# Schematic.net
KiCad netlist of a schematic drawn in Altium Designer
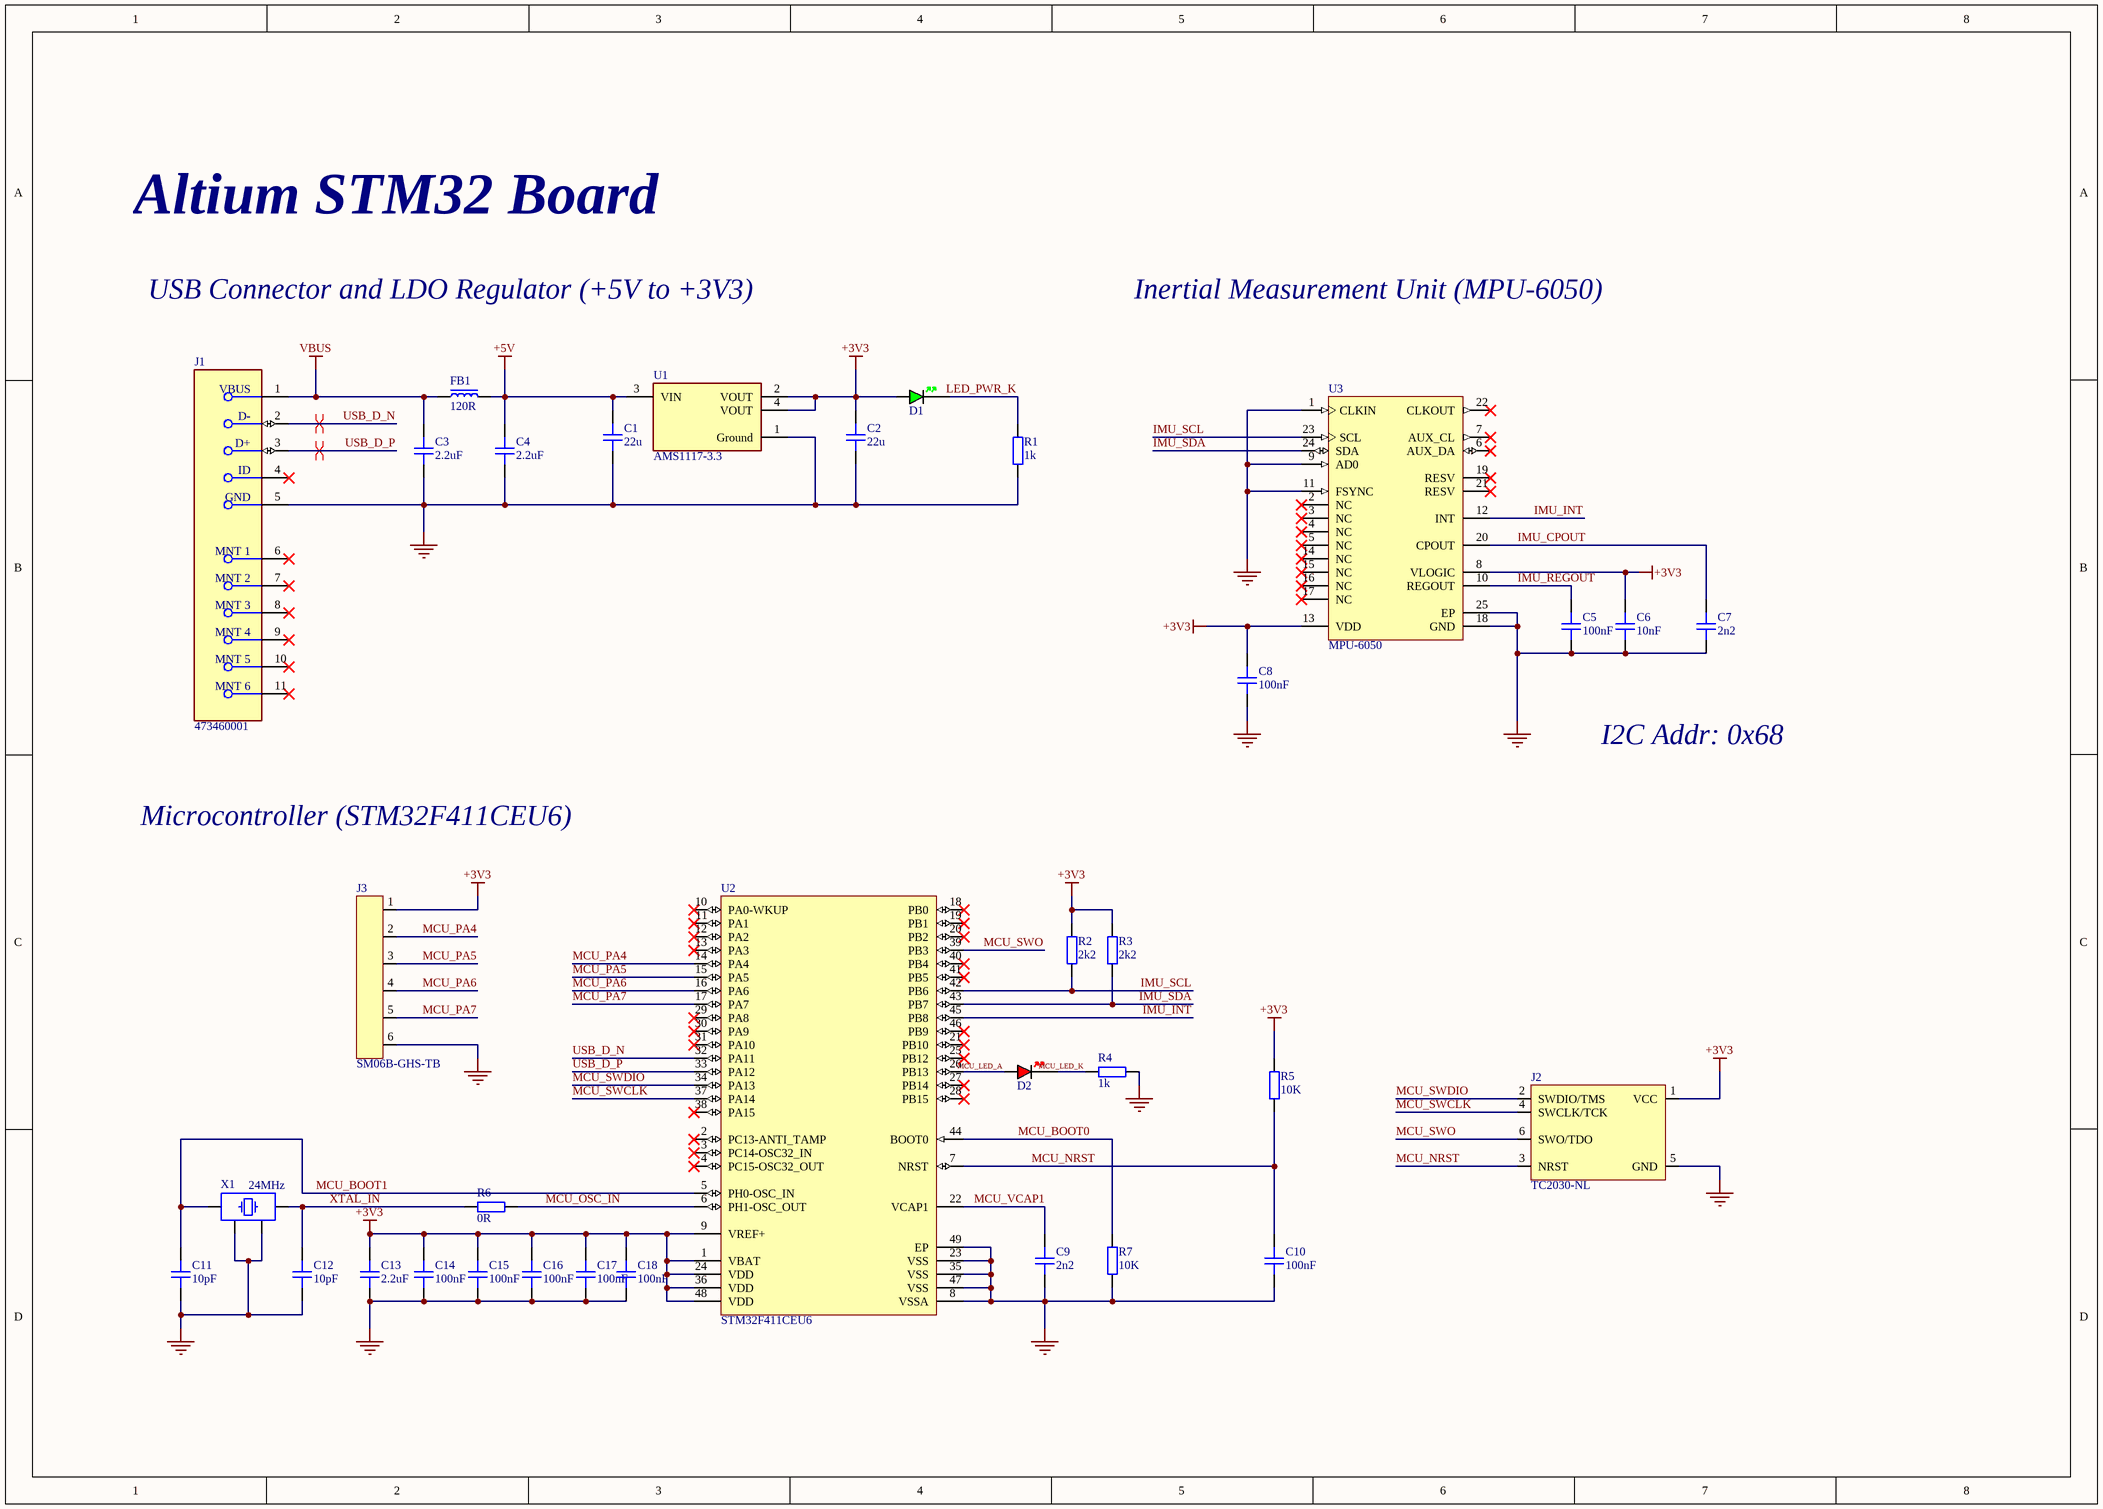
[diagram p0: Schematic.SchDoc]

(export (version "E")
  (design (tool "Eeschema 10.0.6"))
  (components
    (comp (ref "C1")
      (value "22u")
      (footprint "CAP_0805")
      (description "Capacitor SMD 0805 16V")
      (libsource (lib "Schematic-Lib-PhilsLab") (part "CAP_0805_16V"))
    )
    (comp (ref "C2")
      (value "22u")
      (footprint "CAP_0805")
      (description "Capacitor SMD 0805 16V")
      (libsource (lib "Schematic-Lib-PhilsLab") (part "CAP_0805_16V"))
    )
    (comp (ref "C3")
      (value "2.2uF")
      (footprint "CAP_0603")
      (description "Capacitor SMD 0603 16V")
      (libsource (lib "Schematic-Lib-PhilsLab") (part "CAP_0603_16V"))
    )
    (comp (ref "C4")
      (value "2.2uF")
      (footprint "CAP_0603")
      (description "Capacitor SMD 0603 16V")
      (libsource (lib "Schematic-Lib-PhilsLab") (part "CAP_0603_16V"))
    )
    (comp (ref "C5")
      (value "100nF")
      (footprint "CAP_0402")
      (description "Capacitor SMD 0402 16V")
      (libsource (lib "Schematic-Lib-PhilsLab") (part "CAP_0402_16V"))
    )
    (comp (ref "C6")
      (value "10nF")
      (footprint "CAP_0402")
      (description "Capacitor SMD 0402 16V")
      (libsource (lib "Schematic-Lib-PhilsLab") (part "CAP_0402_16V"))
    )
    (comp (ref "C7")
      (value "2n2")
      (footprint "CAP_0402")
      (description "Capacitor SMD 0402 16V")
      (libsource (lib "Schematic-Lib-PhilsLab") (part "CAP_0402_16V"))
    )
    (comp (ref "C8")
      (value "100nF")
      (footprint "CAP_0402")
      (description "Capacitor SMD 0402 16V")
      (libsource (lib "Schematic-Lib-PhilsLab") (part "CAP_0402_16V"))
    )
    (comp (ref "C9")
      (value "2n2")
      (footprint "CAP_0603")
      (description "Capacitor SMD 0603 16V")
      (libsource (lib "Schematic-Lib-PhilsLab") (part "CAP_0603_16V"))
    )
    (comp (ref "C10")
      (value "100nF")
      (footprint "CAP_0402")
      (description "Capacitor SMD 0402 16V")
      (libsource (lib "Schematic-Lib-PhilsLab") (part "CAP_0402_16V"))
    )
    (comp (ref "C11")
      (value "10pF")
      (footprint "CAP_0402")
      (description "Capacitor SMD 0402 16V")
      (libsource (lib "Schematic-Lib-PhilsLab") (part "CAP_0402_16V"))
    )
    (comp (ref "C12")
      (value "10pF")
      (footprint "CAP_0402")
      (description "Capacitor SMD 0402 16V")
      (libsource (lib "Schematic-Lib-PhilsLab") (part "CAP_0402_16V"))
    )
    (comp (ref "C13")
      (value "2.2uF")
      (footprint "CAP_0603")
      (description "Capacitor SMD 0603 16V")
      (libsource (lib "Schematic-Lib-PhilsLab") (part "CAP_0603_16V"))
    )
    (comp (ref "C14")
      (value "100nF")
      (footprint "CAP_0402")
      (description "Capacitor SMD 0402 16V")
      (libsource (lib "Schematic-Lib-PhilsLab") (part "CAP_0402_16V"))
    )
    (comp (ref "C15")
      (value "100nF")
      (footprint "CAP_0402")
      (description "Capacitor SMD 0402 16V")
      (libsource (lib "Schematic-Lib-PhilsLab") (part "CAP_0402_16V"))
    )
    (comp (ref "C16")
      (value "100nF")
      (footprint "CAP_0402")
      (description "Capacitor SMD 0402 16V")
      (libsource (lib "Schematic-Lib-PhilsLab") (part "CAP_0402_16V"))
    )
    (comp (ref "C17")
      (value "100nF")
      (footprint "CAP_0402")
      (description "Capacitor SMD 0402 16V")
      (libsource (lib "Schematic-Lib-PhilsLab") (part "CAP_0402_16V"))
    )
    (comp (ref "C18")
      (value "100nF")
      (footprint "CAP_0402")
      (description "Capacitor SMD 0402 16V")
      (libsource (lib "Schematic-Lib-PhilsLab") (part "CAP_0402_16V"))
    )
    (comp (ref "D1")
      (value "GREEN")
      (footprint "LED_0402_GREEN")
      (description "LED 0402 GREEN SMD")
      (libsource (lib "Schematic-Lib-PhilsLab") (part "LED_0402_GREEN"))
    )
    (comp (ref "D2")
      (value "RED")
      (footprint "LED_0402_RED")
      (description "LED 0402 RED SMD")
      (libsource (lib "Schematic-Lib-PhilsLab") (part "LED_0402_RED"))
    )
    (comp (ref "FB1")
      (value "120R")
      (footprint "FB_0603")
      (description "Ferrite Bead SMD 0603")
      (libsource (lib "Schematic-Lib-PhilsLab") (part "FB_0603"))
    )
    (comp (ref "J1")
      (value "473460001")
      (footprint "FP-473460001-MFG")
      (description "CONN RCPT USB2.0 MICRO B SMD R/A")
      (fields
        (field (name "OCTOPART") "https://octopart.com/47346-0001-molex-7164928")
        (field (name "MANUFACTURER") "Molex")
      )
      (libsource (lib "Altium Content Vault") (part "53ae1f1d9b557310b43ca686e5bb76a"))
    )
    (comp (ref "J2")
      (value "TC2030-NL")
      (footprint "TC2030-NL-FP")
      (description "Tag-Connect No-Solder SWD Debug Connector (No Legs) DO NOT PLACE")
      (fields
        (field (name "MANUFACTURER") "Tag-Connect")
        (field (name "MANUFACTURER PART NUMBER") "TC2030-NL-FP")
      )
      (libsource (lib "Schematic-Lib-PhilsLab") (part "TC2030-NL"))
    )
    (comp (ref "J3")
      (value "SM06B-GHS-TB")
      (footprint "SM06B-GHS-TB")
      (description "Header Connector 6 Position 1.25MM Pitch SMD Horizontal JST GH")
      (fields (field (name "MANUFACTURER") "JST"))
      (libsource (lib "Schematic-Lib-PhilsLab") (part "SM06B-GHS-TB"))
    )
    (comp (ref "R1")
      (value "1k")
      (footprint "RES_0402")
      (description "Resistor SMD 0402")
      (libsource (lib "Schematic-Lib-PhilsLab") (part "RES_0402"))
    )
    (comp (ref "R2")
      (value "2k2")
      (footprint "RES_0402")
      (description "Resistor SMD 0402")
      (libsource (lib "Schematic-Lib-PhilsLab") (part "RES_0402"))
    )
    (comp (ref "R3")
      (value "2k2")
      (footprint "RES_0402")
      (description "Resistor SMD 0402")
      (libsource (lib "Schematic-Lib-PhilsLab") (part "RES_0402"))
    )
    (comp (ref "R4")
      (value "1k")
      (footprint "RES_0402")
      (description "Resistor SMD 0402")
      (libsource (lib "Schematic-Lib-PhilsLab") (part "RES_0402"))
    )
    (comp (ref "R5")
      (value "10K")
      (footprint "RES_0402")
      (description "Resistor SMD 0402")
      (libsource (lib "Schematic-Lib-PhilsLab") (part "RES_0402"))
    )
    (comp (ref "R6")
      (value "0R")
      (footprint "RES_0402")
      (description "Resistor SMD 0402")
      (libsource (lib "Schematic-Lib-PhilsLab") (part "RES_0402"))
    )
    (comp (ref "R7")
      (value "10K")
      (footprint "RES_0402")
      (description "Resistor SMD 0402")
      (libsource (lib "Schematic-Lib-PhilsLab") (part "RES_0402"))
    )
    (comp (ref "U1")
      (value "AMS1117-3.3")
      (footprint "FP-AMS1117-IPC_C")
      (description "LDO Voltage Regulators 1A, 3.3V")
      (fields
        (field (name "OCTOPART") "https://octopart.com/ams1117-3.3-advanced+monolithic+systems-25899300")
        (field (name "MANUFACTURER") "Advanced Monolithic Systems")
      )
      (libsource (lib "Altium Content Vault") (part "8bdbb5f8e77002000e30dd2845d0354"))
    )
    (comp (ref "U2")
      (value "STM32F411CEU6")
      (footprint "STM-UFQFPN48_L")
      (libsource (lib "Altium Content Vault") (part "MC-ARM-STM32F411-UFQFPN48"))
    )
    (comp (ref "U3")
      (value "MPU-6050")
      (footprint "IS-QFN-24_V")
      (fields (field (name "MANUFACTURER") "InvenSense"))
      (libsource (lib "Altium Content Vault") (part "IS-MPU-6050-QFN-24"))
    )
    (comp (ref "X1")
      (value "24MHz")
      (footprint "XTAL_3225")
      (description "Crystal SMD 24MHz 10PPM 7pF 3225")
      (fields
        (field (name "MANUFACTURER") "Epson")
        (field (name "MANUFACTURER PART NUMBER") "TSX-3225 24.0000MF15X-AC")
      )
      (libsource (lib "Schematic-Lib-PhilsLab") (part "TSX-3225_24.0000MF15X-AC"))
    )
  )
  (nets
    (net (code "1") (name "+3V3") (class "Default")
      (node (ref "C13") (pin "2") (pinfunction "2_2") (pintype "passive"))
      (node (ref "C14") (pin "2") (pinfunction "2_2") (pintype "passive"))
      (node (ref "C15") (pin "2") (pinfunction "2_2") (pintype "passive"))
      (node (ref "C16") (pin "2") (pinfunction "2_2") (pintype "passive"))
      (node (ref "C17") (pin "2") (pinfunction "2_2") (pintype "passive"))
      (node (ref "C18") (pin "2") (pinfunction "2_2") (pintype "passive"))
      (node (ref "C2") (pin "2") (pinfunction "2_2") (pintype "passive"))
      (node (ref "C6") (pin "2") (pinfunction "2_2") (pintype "passive"))
      (node (ref "C8") (pin "2") (pinfunction "2_2") (pintype "passive"))
      (node (ref "D1") (pin "A") (pinfunction "A_A") (pintype "passive"))
      (node (ref "J2") (pin "1") (pinfunction "VCC_1") (pintype "passive"))
      (node (ref "J3") (pin "1") (pinfunction "1_1") (pintype "passive"))
      (node (ref "R2") (pin "2") (pinfunction "2_2") (pintype "passive"))
      (node (ref "R3") (pin "2") (pinfunction "2_2") (pintype "passive"))
      (node (ref "R5") (pin "2") (pinfunction "2_2") (pintype "passive"))
      (node (ref "U1") (pin "2") (pinfunction "VOUT_2") (pintype "passive"))
      (node (ref "U1") (pin "4") (pinfunction "VOUT_4") (pintype "passive"))
      (node (ref "U2") (pin "1") (pinfunction "VBAT_1") (pintype "power_in"))
      (node (ref "U2") (pin "24") (pinfunction "VDD_24") (pintype "power_in"))
      (node (ref "U2") (pin "36") (pinfunction "VDD_36") (pintype "power_in"))
      (node (ref "U2") (pin "48") (pinfunction "VDD_48") (pintype "power_in"))
      (node (ref "U2") (pin "9") (pinfunction "VREF+_9") (pintype "power_in"))
      (node (ref "U3") (pin "13") (pinfunction "VDD_13") (pintype "power_in"))
      (node (ref "U3") (pin "8") (pinfunction "VLOGIC_8") (pintype "power_in"))
    )
    (net (code "2") (name "+5V") (class "Default")
      (node (ref "C1") (pin "2") (pinfunction "2_2") (pintype "passive"))
      (node (ref "C4") (pin "2") (pinfunction "2_2") (pintype "passive"))
      (node (ref "FB1") (pin "2") (pinfunction "2_2") (pintype "passive"))
      (node (ref "U1") (pin "3") (pinfunction "VIN_3") (pintype "power_in"))
    )
    (net (code "3") (name "/IMU_CPOUT") (class "Default")
      (node (ref "C7") (pin "2") (pinfunction "2_2") (pintype "passive"))
      (node (ref "U3") (pin "20") (pinfunction "CPOUT_20") (pintype "passive"))
    )
    (net (code "4") (name "/IMU_INT") (class "Default")
      (node (ref "U2") (pin "45") (pinfunction "PB8_45") (pintype "bidirectional"))
      (node (ref "U3") (pin "12") (pinfunction "INT_12") (pintype "open_collector"))
    )
    (net (code "5") (name "/IMU_REGOUT") (class "Default")
      (node (ref "C5") (pin "2") (pinfunction "2_2") (pintype "passive"))
      (node (ref "U3") (pin "10") (pinfunction "REGOUT_10") (pintype "passive"))
    )
    (net (code "6") (name "/IMU_SCL") (class "Default")
      (node (ref "R2") (pin "1") (pinfunction "1_1") (pintype "passive"))
      (node (ref "U2") (pin "42") (pinfunction "PB6_42") (pintype "bidirectional"))
      (node (ref "U3") (pin "23") (pinfunction "SCL_23") (pintype "input"))
    )
    (net (code "7") (name "/IMU_SDA") (class "Default")
      (node (ref "R3") (pin "1") (pinfunction "1_1") (pintype "passive"))
      (node (ref "U2") (pin "43") (pinfunction "PB7_43") (pintype "bidirectional"))
      (node (ref "U3") (pin "24") (pinfunction "SDA_24") (pintype "bidirectional"))
    )
    (net (code "8") (name "/LED_PWR_K") (class "Default")
      (node (ref "D1") (pin "K") (pinfunction "K_K") (pintype "passive"))
      (node (ref "R1") (pin "2") (pinfunction "2_2") (pintype "passive"))
    )
    (net (code "9") (name "/MCU_BOOT0") (class "Default")
      (node (ref "R7") (pin "2") (pinfunction "2_2") (pintype "passive"))
      (node (ref "U2") (pin "44") (pinfunction "BOOT0_44") (pintype "input"))
    )
    (net (code "10") (name "/MCU_BOOT1") (class "Default")
      (node (ref "C11") (pin "2") (pinfunction "2_2") (pintype "passive"))
      (node (ref "U2") (pin "5") (pinfunction "PH0-OSC_IN_5") (pintype "bidirectional"))
      (node (ref "X1") (pin "1") (pinfunction "1_1") (pintype "passive"))
    )
    (net (code "11") (name "/MCU_LED_A") (class "Default")
      (node (ref "D2") (pin "A") (pinfunction "A_A") (pintype "passive"))
      (node (ref "U2") (pin "26") (pinfunction "PB13_26") (pintype "bidirectional"))
    )
    (net (code "12") (name "/MCU_LED_K") (class "Default")
      (node (ref "D2") (pin "K") (pinfunction "K_K") (pintype "passive"))
      (node (ref "R4") (pin "2") (pinfunction "2_2") (pintype "passive"))
    )
    (net (code "13") (name "/MCU_NRST") (class "Default")
      (node (ref "C10") (pin "2") (pinfunction "2_2") (pintype "passive"))
      (node (ref "J2") (pin "3") (pinfunction "NRST_3") (pintype "passive"))
      (node (ref "R5") (pin "1") (pinfunction "1_1") (pintype "passive"))
      (node (ref "U2") (pin "7") (pinfunction "NRST_7") (pintype "bidirectional"))
    )
    (net (code "14") (name "/MCU_OSC_IN") (class "Default")
      (node (ref "R6") (pin "2") (pinfunction "2_2") (pintype "passive"))
      (node (ref "U2") (pin "6") (pinfunction "PH1-OSC_OUT_6") (pintype "bidirectional"))
    )
    (net (code "15") (name "/MCU_PA4") (class "Default")
      (node (ref "J3") (pin "2") (pinfunction "2_2") (pintype "passive"))
      (node (ref "U2") (pin "14") (pinfunction "PA4_14") (pintype "bidirectional"))
    )
    (net (code "16") (name "/MCU_PA5") (class "Default")
      (node (ref "J3") (pin "3") (pinfunction "3_3") (pintype "passive"))
      (node (ref "U2") (pin "15") (pinfunction "PA5_15") (pintype "bidirectional"))
    )
    (net (code "17") (name "/MCU_PA6") (class "Default")
      (node (ref "J3") (pin "4") (pinfunction "4_4") (pintype "passive"))
      (node (ref "U2") (pin "16") (pinfunction "PA6_16") (pintype "bidirectional"))
    )
    (net (code "18") (name "/MCU_PA7") (class "Default")
      (node (ref "J3") (pin "5") (pinfunction "5_5") (pintype "passive"))
      (node (ref "U2") (pin "17") (pinfunction "PA7_17") (pintype "bidirectional"))
    )
    (net (code "19") (name "/MCU_SWCLK") (class "Default")
      (node (ref "J2") (pin "4") (pinfunction "SWCLK/TCK_4") (pintype "passive"))
      (node (ref "U2") (pin "37") (pinfunction "PA14_37") (pintype "bidirectional"))
    )
    (net (code "20") (name "/MCU_SWDIO") (class "Default")
      (node (ref "J2") (pin "2") (pinfunction "SWDIO/TMS_2") (pintype "passive"))
      (node (ref "U2") (pin "34") (pinfunction "PA13_34") (pintype "bidirectional"))
    )
    (net (code "21") (name "/MCU_SWO") (class "Default")
      (node (ref "J2") (pin "6") (pinfunction "SWO/TDO_6") (pintype "passive"))
      (node (ref "U2") (pin "39") (pinfunction "PB3_39") (pintype "bidirectional"))
    )
    (net (code "22") (name "/MCU_VCAP1") (class "Default")
      (node (ref "C9") (pin "2") (pinfunction "2_2") (pintype "passive"))
      (node (ref "U2") (pin "22") (pinfunction "VCAP1_22") (pintype "passive"))
    )
    (net (code "23") (name "/USB_D_N") (class "Default")
      (node (ref "J1") (pin "2") (pinfunction "D-_2") (pintype "bidirectional"))
      (node (ref "U2") (pin "32") (pinfunction "PA11_32") (pintype "bidirectional"))
    )
    (net (code "24") (name "/USB_D_P") (class "Default")
      (node (ref "J1") (pin "3") (pinfunction "D+_3") (pintype "bidirectional"))
      (node (ref "U2") (pin "33") (pinfunction "PA12_33") (pintype "bidirectional"))
    )
    (net (code "25") (name "/XTAL_IN") (class "Default")
      (node (ref "C12") (pin "2") (pinfunction "2_2") (pintype "passive"))
      (node (ref "R6") (pin "1") (pinfunction "1_1") (pintype "passive"))
      (node (ref "X1") (pin "3") (pinfunction "3_3") (pintype "passive"))
    )
    (net (code "26") (name "GND") (class "Default")
      (node (ref "C1") (pin "1") (pinfunction "1_1") (pintype "passive"))
      (node (ref "C10") (pin "1") (pinfunction "1_1") (pintype "passive"))
      (node (ref "C11") (pin "1") (pinfunction "1_1") (pintype "passive"))
      (node (ref "C12") (pin "1") (pinfunction "1_1") (pintype "passive"))
      (node (ref "C13") (pin "1") (pinfunction "1_1") (pintype "passive"))
      (node (ref "C14") (pin "1") (pinfunction "1_1") (pintype "passive"))
      (node (ref "C15") (pin "1") (pinfunction "1_1") (pintype "passive"))
      (node (ref "C16") (pin "1") (pinfunction "1_1") (pintype "passive"))
      (node (ref "C17") (pin "1") (pinfunction "1_1") (pintype "passive"))
      (node (ref "C18") (pin "1") (pinfunction "1_1") (pintype "passive"))
      (node (ref "C2") (pin "1") (pinfunction "1_1") (pintype "passive"))
      (node (ref "C3") (pin "1") (pinfunction "1_1") (pintype "passive"))
      (node (ref "C4") (pin "1") (pinfunction "1_1") (pintype "passive"))
      (node (ref "C5") (pin "1") (pinfunction "1_1") (pintype "passive"))
      (node (ref "C6") (pin "1") (pinfunction "1_1") (pintype "passive"))
      (node (ref "C7") (pin "1") (pinfunction "1_1") (pintype "passive"))
      (node (ref "C8") (pin "1") (pinfunction "1_1") (pintype "passive"))
      (node (ref "C9") (pin "1") (pinfunction "1_1") (pintype "passive"))
      (node (ref "J1") (pin "5") (pinfunction "GND_5") (pintype "power_in"))
      (node (ref "J2") (pin "5") (pinfunction "GND_5") (pintype "passive"))
      (node (ref "J3") (pin "6") (pinfunction "6_6") (pintype "passive"))
      (node (ref "R1") (pin "1") (pinfunction "1_1") (pintype "passive"))
      (node (ref "R4") (pin "1") (pinfunction "1_1") (pintype "passive"))
      (node (ref "R7") (pin "1") (pinfunction "1_1") (pintype "passive"))
      (node (ref "U1") (pin "1") (pinfunction "Ground_1") (pintype "power_in"))
      (node (ref "U2") (pin "23") (pinfunction "VSS_23") (pintype "power_in"))
      (node (ref "U2") (pin "35") (pinfunction "VSS_35") (pintype "power_in"))
      (node (ref "U2") (pin "47") (pinfunction "VSS_47") (pintype "power_in"))
      (node (ref "U2") (pin "49") (pinfunction "EP_49") (pintype "power_in"))
      (node (ref "U2") (pin "8") (pinfunction "VSSA_8") (pintype "power_in"))
      (node (ref "U3") (pin "1") (pinfunction "CLKIN_1") (pintype "input"))
      (node (ref "U3") (pin "11") (pinfunction "FSYNC_11") (pintype "input"))
      (node (ref "U3") (pin "18") (pinfunction "GND_18") (pintype "power_in"))
      (node (ref "U3") (pin "25") (pinfunction "EP_25") (pintype "power_in"))
      (node (ref "U3") (pin "9") (pinfunction "AD0_9") (pintype "input"))
      (node (ref "X1") (pin "2") (pinfunction "2_2") (pintype "passive"))
      (node (ref "X1") (pin "4") (pinfunction "4_4") (pintype "passive"))
    )
    (net (code "27") (name "VBUS") (class "Default")
      (node (ref "C3") (pin "2") (pinfunction "2_2") (pintype "passive"))
      (node (ref "FB1") (pin "1") (pinfunction "1_1") (pintype "passive"))
      (node (ref "J1") (pin "1") (pinfunction "VBUS_1") (pintype "power_in"))
    )
    (net (code "28") (name "unconnected-(J1-ID-Pad4)") (class "Default")
      (node (ref "J1") (pin "4") (pinfunction "ID_4") (pintype "passive+no_connect"))
    )
    (net (code "29") (name "unconnected-(J1-MNT_1-Pad6)") (class "Default")
      (node (ref "J1") (pin "6") (pinfunction "MNT_1_6") (pintype "passive+no_connect"))
    )
    (net (code "30") (name "unconnected-(J1-MNT_2-Pad7)") (class "Default")
      (node (ref "J1") (pin "7") (pinfunction "MNT_2_7") (pintype "passive+no_connect"))
    )
    (net (code "31") (name "unconnected-(J1-MNT_3-Pad8)") (class "Default")
      (node (ref "J1") (pin "8") (pinfunction "MNT_3_8") (pintype "passive+no_connect"))
    )
    (net (code "32") (name "unconnected-(J1-MNT_4-Pad9)") (class "Default")
      (node (ref "J1") (pin "9") (pinfunction "MNT_4_9") (pintype "passive+no_connect"))
    )
    (net (code "33") (name "unconnected-(J1-MNT_5-Pad10)") (class "Default")
      (node (ref "J1") (pin "10") (pinfunction "MNT_5_10") (pintype "passive+no_connect"))
    )
    (net (code "34") (name "unconnected-(J1-MNT_6-Pad11)") (class "Default")
      (node (ref "J1") (pin "11") (pinfunction "MNT_6_11") (pintype "passive+no_connect"))
    )
    (net (code "35") (name "unconnected-(U2-PA0-WKUP-Pad10)") (class "Default")
      (node (ref "U2") (pin "10") (pinfunction "PA0-WKUP_10") (pintype "bidirectional+no_connect"))
    )
    (net (code "36") (name "unconnected-(U2-PA1-Pad11)") (class "Default")
      (node (ref "U2") (pin "11") (pinfunction "PA1_11") (pintype "bidirectional+no_connect"))
    )
    (net (code "37") (name "unconnected-(U2-PA2-Pad12)") (class "Default")
      (node (ref "U2") (pin "12") (pinfunction "PA2_12") (pintype "bidirectional+no_connect"))
    )
    (net (code "38") (name "unconnected-(U2-PA3-Pad13)") (class "Default")
      (node (ref "U2") (pin "13") (pinfunction "PA3_13") (pintype "bidirectional+no_connect"))
    )
    (net (code "39") (name "unconnected-(U2-PA8-Pad29)") (class "Default")
      (node (ref "U2") (pin "29") (pinfunction "PA8_29") (pintype "bidirectional+no_connect"))
    )
    (net (code "40") (name "unconnected-(U2-PA9-Pad30)") (class "Default")
      (node (ref "U2") (pin "30") (pinfunction "PA9_30") (pintype "bidirectional+no_connect"))
    )
    (net (code "41") (name "unconnected-(U2-PA10-Pad31)") (class "Default")
      (node (ref "U2") (pin "31") (pinfunction "PA10_31") (pintype "bidirectional+no_connect"))
    )
    (net (code "42") (name "unconnected-(U2-PA15-Pad38)") (class "Default")
      (node (ref "U2") (pin "38") (pinfunction "PA15_38") (pintype "bidirectional+no_connect"))
    )
    (net (code "43") (name "unconnected-(U2-PB0-Pad18)") (class "Default")
      (node (ref "U2") (pin "18") (pinfunction "PB0_18") (pintype "bidirectional+no_connect"))
    )
    (net (code "44") (name "unconnected-(U2-PB1-Pad19)") (class "Default")
      (node (ref "U2") (pin "19") (pinfunction "PB1_19") (pintype "bidirectional+no_connect"))
    )
    (net (code "45") (name "unconnected-(U2-PB2-Pad20)") (class "Default")
      (node (ref "U2") (pin "20") (pinfunction "PB2_20") (pintype "bidirectional+no_connect"))
    )
    (net (code "46") (name "unconnected-(U2-PB4-Pad40)") (class "Default")
      (node (ref "U2") (pin "40") (pinfunction "PB4_40") (pintype "bidirectional+no_connect"))
    )
    (net (code "47") (name "unconnected-(U2-PB5-Pad41)") (class "Default")
      (node (ref "U2") (pin "41") (pinfunction "PB5_41") (pintype "bidirectional+no_connect"))
    )
    (net (code "48") (name "unconnected-(U2-PB9-Pad46)") (class "Default")
      (node (ref "U2") (pin "46") (pinfunction "PB9_46") (pintype "bidirectional+no_connect"))
    )
    (net (code "49") (name "unconnected-(U2-PB10-Pad21)") (class "Default")
      (node (ref "U2") (pin "21") (pinfunction "PB10_21") (pintype "bidirectional+no_connect"))
    )
    (net (code "50") (name "unconnected-(U2-PB12-Pad25)") (class "Default")
      (node (ref "U2") (pin "25") (pinfunction "PB12_25") (pintype "bidirectional+no_connect"))
    )
    (net (code "51") (name "unconnected-(U2-PB14-Pad27)") (class "Default")
      (node (ref "U2") (pin "27") (pinfunction "PB14_27") (pintype "bidirectional+no_connect"))
    )
    (net (code "52") (name "unconnected-(U2-PB15-Pad28)") (class "Default")
      (node (ref "U2") (pin "28") (pinfunction "PB15_28") (pintype "bidirectional+no_connect"))
    )
    (net (code "53") (name "unconnected-(U2-PC13-ANTI_TAMP-Pad2)") (class "Default")
      (node (ref "U2") (pin "2") (pinfunction "PC13-ANTI_TAMP_2") (pintype "bidirectional+no_connect"))
    )
    (net (code "54") (name "unconnected-(U2-PC14-OSC32_IN-Pad3)") (class "Default")
      (node (ref "U2") (pin "3") (pinfunction "PC14-OSC32_IN_3") (pintype "bidirectional+no_connect"))
    )
    (net (code "55") (name "unconnected-(U2-PC15-OSC32_OUT-Pad4)") (class "Default")
      (node (ref "U2") (pin "4") (pinfunction "PC15-OSC32_OUT_4") (pintype "bidirectional+no_connect"))
    )
    (net (code "56") (name "unconnected-(U3-AUX_CL-Pad7)") (class "Default")
      (node (ref "U3") (pin "7") (pinfunction "AUX_CL_7") (pintype "output+no_connect"))
    )
    (net (code "57") (name "unconnected-(U3-AUX_DA-Pad6)") (class "Default")
      (node (ref "U3") (pin "6") (pinfunction "AUX_DA_6") (pintype "bidirectional+no_connect"))
    )
    (net (code "58") (name "unconnected-(U3-CLKOUT-Pad22)") (class "Default")
      (node (ref "U3") (pin "22") (pinfunction "CLKOUT_22") (pintype "output+no_connect"))
    )
    (net (code "59") (name "unconnected-(U3-NC-Pad2)") (class "Default")
      (node (ref "U3") (pin "2") (pinfunction "NC_2") (pintype "passive+no_connect"))
    )
    (net (code "60") (name "unconnected-(U3-NC-Pad3)") (class "Default")
      (node (ref "U3") (pin "3") (pinfunction "NC_3") (pintype "passive+no_connect"))
    )
    (net (code "61") (name "unconnected-(U3-NC-Pad4)") (class "Default")
      (node (ref "U3") (pin "4") (pinfunction "NC_4") (pintype "passive+no_connect"))
    )
    (net (code "62") (name "unconnected-(U3-NC-Pad5)") (class "Default")
      (node (ref "U3") (pin "5") (pinfunction "NC_5") (pintype "passive+no_connect"))
    )
    (net (code "63") (name "unconnected-(U3-NC-Pad14)") (class "Default")
      (node (ref "U3") (pin "14") (pinfunction "NC_14") (pintype "passive+no_connect"))
    )
    (net (code "64") (name "unconnected-(U3-NC-Pad15)") (class "Default")
      (node (ref "U3") (pin "15") (pinfunction "NC_15") (pintype "passive+no_connect"))
    )
    (net (code "65") (name "unconnected-(U3-NC-Pad16)") (class "Default")
      (node (ref "U3") (pin "16") (pinfunction "NC_16") (pintype "passive+no_connect"))
    )
    (net (code "66") (name "unconnected-(U3-NC-Pad17)") (class "Default")
      (node (ref "U3") (pin "17") (pinfunction "NC_17") (pintype "passive+no_connect"))
    )
    (net (code "67") (name "unconnected-(U3-RESV-Pad19)") (class "Default")
      (node (ref "U3") (pin "19") (pinfunction "RESV_19") (pintype "passive+no_connect"))
    )
    (net (code "68") (name "unconnected-(U3-RESV-Pad21)") (class "Default")
      (node (ref "U3") (pin "21") (pinfunction "RESV_21") (pintype "passive+no_connect"))
    )
  )
)
